# Sensor_Power_Supply.net
KiCad netlist of a schematic drawn in Altium Designer
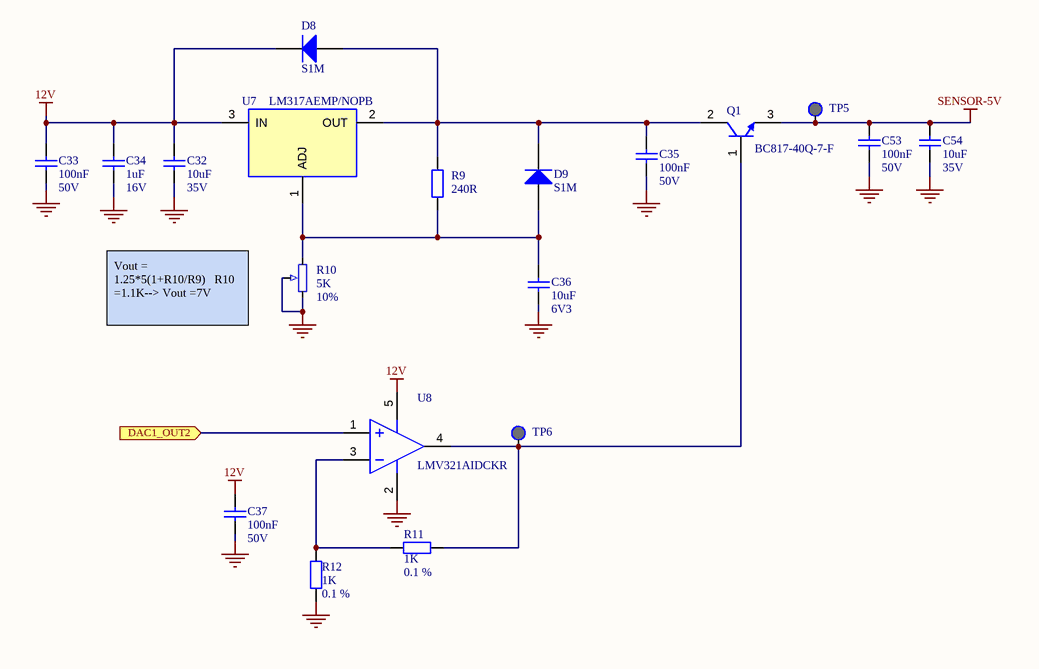
[diagram p0: Sensor Power Supply.SchDoc]

(export (version "E")
  (design (tool "Eeschema 10.0.6"))
  (components
    (comp (ref "C32")
      (value "Capacitor")
      (footprint "CAPC1608N")
      (fields
        (field (name "PART NUMBER") "CAP-000000006")
        (field (name "VALUE 1") "10uF")
        (field (name "VALUE 2") "35V")
      )
      (libsource (lib "CMA") (part "Capacitor"))
    )
    (comp (ref "C33")
      (value "Capacitor")
      (footprint "CAPC1608N")
      (fields
        (field (name "PART NUMBER") "CAP-000000002")
        (field (name "VALUE 1") "100nF")
        (field (name "VALUE 2") "50V")
      )
      (libsource (lib "CMA") (part "Capacitor"))
    )
    (comp (ref "C34")
      (value "Capacitor")
      (footprint "CAPC1608N")
      (fields
        (field (name "PART NUMBER") "CAP-000000011")
        (field (name "VALUE 1") "1uF")
        (field (name "VALUE 2") "16V")
      )
      (libsource (lib "CMA") (part "Capacitor"))
    )
    (comp (ref "C35")
      (value "Capacitor")
      (footprint "CAPC1608N")
      (fields
        (field (name "PART NUMBER") "CAP-000000002")
        (field (name "VALUE 1") "100nF")
        (field (name "VALUE 2") "50V")
      )
      (libsource (lib "CMA") (part "Capacitor"))
    )
    (comp (ref "C36")
      (value "Capacitor")
      (footprint "CAPC2012N")
      (fields
        (field (name "PART NUMBER") "CAP-000000001")
        (field (name "VALUE 1") "10uF")
        (field (name "VALUE 2") "6V3")
      )
      (libsource (lib "CMA") (part "Capacitor"))
    )
    (comp (ref "C37")
      (value "Capacitor")
      (footprint "CAPC1608N")
      (fields
        (field (name "PART NUMBER") "CAP-000000002")
        (field (name "VALUE 1") "100nF")
        (field (name "VALUE 2") "50V")
      )
      (libsource (lib "CMA") (part "Capacitor"))
    )
    (comp (ref "C53")
      (value "Capacitor")
      (footprint "CAPC1608N")
      (fields
        (field (name "PART NUMBER") "CAP-000000002")
        (field (name "VALUE 1") "100nF")
        (field (name "VALUE 2") "50V")
      )
      (libsource (lib "CMA") (part "Capacitor"))
    )
    (comp (ref "C54")
      (value "Capacitor")
      (footprint "CAPC1608N")
      (fields
        (field (name "PART NUMBER") "CAP-000000006")
        (field (name "VALUE 1") "10uF")
        (field (name "VALUE 2") "35V")
      )
      (libsource (lib "CMA") (part "Capacitor"))
    )
    (comp (ref "D8")
      (value "S1M")
      (footprint "DIOM5227X270N")
      (fields (field (name "PART NUMBER") "DIR-000000001"))
      (libsource (lib "CMA") (part "Diode"))
    )
    (comp (ref "D9")
      (value "S1M")
      (footprint "DIOM5227X270N")
      (fields (field (name "PART NUMBER") "DIR-000000001"))
      (libsource (lib "CMA") (part "Diode"))
    )
    (comp (ref "Q1")
      (value "BC817-40Q-7-F")
      (footprint "SOT23-3N")
      (fields (field (name "PART NUMBER") "TRP-000000008"))
      (libsource (lib "CMA") (part "NPN1"))
    )
    (comp (ref "R9")
      (value "Resistor")
      (footprint "RESC1608N")
      (fields (field (name "PART NUMBER") "RES-000000110") (field (name "VALUE 1") "240R"))
      (libsource (lib "CMA") (part "Resistor"))
    )
    (comp (ref "R10")
      (value "3296W-1-502RLF")
      (footprint "3296W-1-502RLF")
      (fields
        (field (name "PART NUMBER") "RES-000000111")
        (field (name "VALUE 1") "5K")
        (field (name "TOL") "10%")
      )
      (libsource (lib "CMA") (part "RPot"))
    )
    (comp (ref "R11")
      (value "Resistor")
      (footprint "RESC1608N")
      (fields
        (field (name "PART NUMBER") "RES-000000112")
        (field (name "VALUE 1") "1K")
        (field (name "TOL") "0.1 %")
      )
      (libsource (lib "") (part "Resistor_2"))
    )
    (comp (ref "R12")
      (value "Resistor")
      (footprint "RESC1608N")
      (fields
        (field (name "PART NUMBER") "RES-000000112")
        (field (name "VALUE 1") "1K")
        (field (name "TOL") "0.1 %")
      )
      (libsource (lib "") (part "Resistor_1"))
    )
    (comp (ref "TP5")
      (value "Test Point")
      (footprint "TP")
      (fields (field (name "PART NUMBER") "MIS-000000003"))
      (libsource (lib "CMA") (part "TP"))
    )
    (comp (ref "TP6")
      (value "Test Point")
      (footprint "TP")
      (fields (field (name "PART NUMBER") "MIS-000000003"))
      (libsource (lib "CMA") (part "TP"))
    )
    (comp (ref "U7")
      (value "LM317AEMP/NOPB")
      (footprint "SOT-223-4")
      (fields (field (name "PART NUMBER") "VRG-000000016"))
      (libsource (lib "CMA") (part "LM317"))
    )
    (comp (ref "U8")
      (value "LMV321AIDCKR")
      (footprint "SC-70-5")
      (fields (field (name "PART NUMBER") "OPA-000000001"))
      (libsource (lib "CMA") (part "LMV321AIDCKR"))
    )
  )
  (nets
    (net (code "1") (name "/DAC1_OUT2") (class "Default")
      (node (ref "U8") (pin "1") (pinfunction "+IN_1") (pintype "passive"))
    )
    (net (code "2") (name "12V") (class "Default")
      (node (ref "C32") (pin "1") (pinfunction "1_1") (pintype "passive"))
      (node (ref "C33") (pin "1") (pinfunction "1_1") (pintype "passive"))
      (node (ref "C34") (pin "1") (pinfunction "1_1") (pintype "passive"))
      (node (ref "C37") (pin "1") (pinfunction "1_1") (pintype "passive"))
      (node (ref "D8") (pin "1") (pinfunction "K_1") (pintype "passive"))
      (node (ref "U7") (pin "3") (pinfunction "IN_3") (pintype "passive"))
      (node (ref "U8") (pin "5") (pinfunction "+V_5") (pintype "power_in"))
    )
    (net (code "3") (name "GND") (class "Default")
      (node (ref "C32") (pin "2") (pinfunction "2_2") (pintype "passive"))
      (node (ref "C33") (pin "2") (pinfunction "2_2") (pintype "passive"))
      (node (ref "C34") (pin "2") (pinfunction "2_2") (pintype "passive"))
      (node (ref "C35") (pin "2") (pinfunction "2_2") (pintype "passive"))
      (node (ref "C36") (pin "2") (pinfunction "2_2") (pintype "passive"))
      (node (ref "C37") (pin "2") (pinfunction "2_2") (pintype "passive"))
      (node (ref "C53") (pin "2") (pinfunction "2_2") (pintype "passive"))
      (node (ref "C54") (pin "2") (pinfunction "2_2") (pintype "passive"))
      (node (ref "R10") (pin "2") (pinfunction "2_2") (pintype "passive"))
      (node (ref "R10") (pin "3") (pinfunction "3_3") (pintype "passive"))
      (node (ref "R12") (pin "2") (pinfunction "2_2") (pintype "passive"))
      (node (ref "U8") (pin "2") (pinfunction "-V_2") (pintype "power_in"))
    )
    (net (code "4") (name "Net-(D8-A)") (class "Default")
      (node (ref "C35") (pin "1") (pinfunction "1_1") (pintype "passive"))
      (node (ref "D8") (pin "2") (pinfunction "A_2") (pintype "passive"))
      (node (ref "D9") (pin "1") (pinfunction "K_1") (pintype "passive"))
      (node (ref "Q1") (pin "2") (pinfunction "C_2") (pintype "passive"))
      (node (ref "R9") (pin "2") (pinfunction "2_2") (pintype "passive"))
      (node (ref "U7") (pin "2") (pinfunction "OUT_2") (pintype "passive"))
    )
    (net (code "5") (name "Net-(D9-A)") (class "Default")
      (node (ref "C36") (pin "1") (pinfunction "1_1") (pintype "passive"))
      (node (ref "D9") (pin "2") (pinfunction "A_2") (pintype "passive"))
      (node (ref "R10") (pin "1") (pinfunction "1_1") (pintype "passive"))
      (node (ref "R9") (pin "1") (pinfunction "1_1") (pintype "passive"))
      (node (ref "U7") (pin "1") (pinfunction "ADJ_1") (pintype "passive"))
    )
    (net (code "6") (name "Net-(Q1-B)") (class "Default")
      (node (ref "Q1") (pin "1") (pinfunction "B_1") (pintype "passive"))
      (node (ref "R11") (pin "1") (pinfunction "1_1") (pintype "passive"))
      (node (ref "TP6") (pin "1") (pinfunction "1_1") (pintype "passive"))
      (node (ref "U8") (pin "4") (pinfunction "OUT_4") (pintype "passive"))
    )
    (net (code "7") (name "Net-(U8--IN)") (class "Default")
      (node (ref "R11") (pin "2") (pinfunction "2_2") (pintype "passive"))
      (node (ref "R12") (pin "1") (pinfunction "1_1") (pintype "passive"))
      (node (ref "U8") (pin "3") (pinfunction "-IN_3") (pintype "passive"))
    )
    (net (code "8") (name "SENSOR-5V") (class "Default")
      (node (ref "C53") (pin "1") (pinfunction "1_1") (pintype "passive"))
      (node (ref "C54") (pin "1") (pinfunction "1_1") (pintype "passive"))
      (node (ref "Q1") (pin "3") (pinfunction "E_3") (pintype "passive"))
      (node (ref "TP5") (pin "1") (pinfunction "1_1") (pintype "passive"))
    )
  )
)
